# 04_Serial_Console.net
KiCad netlist of a schematic drawn in Altium Designer
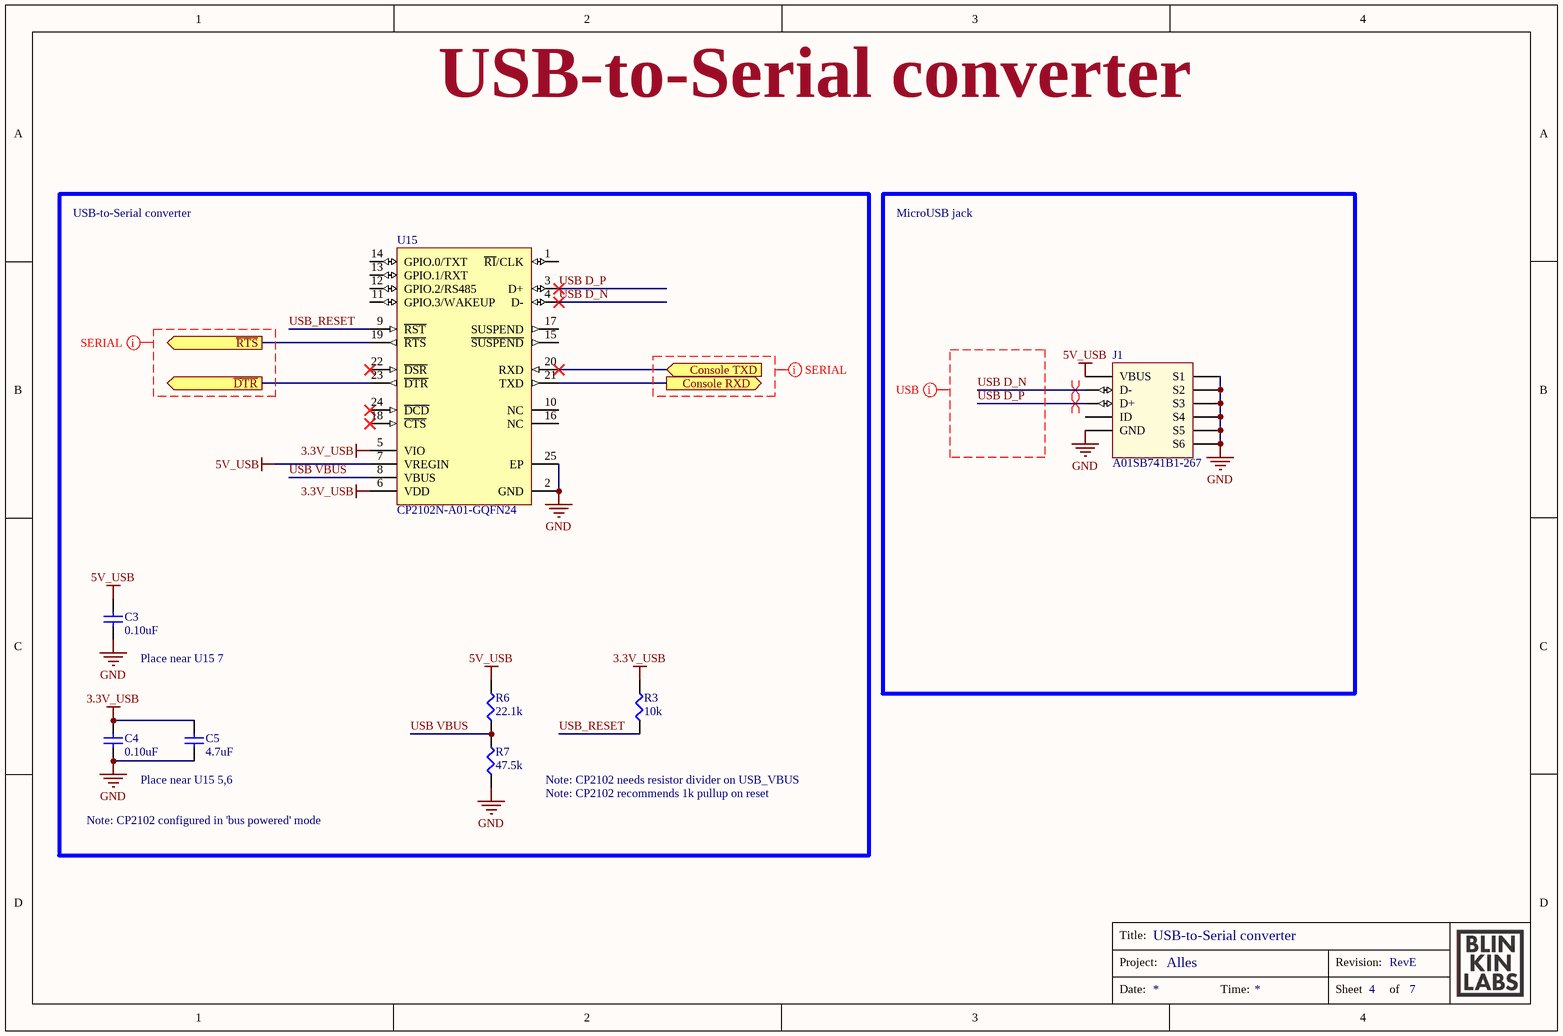
[diagram p0: [04] Serial Console.SchDoc]

(export (version "E")
  (design (tool "Eeschema 10.0.6"))
  (components
    (comp (ref "C3")
      (value "0.10uF")
      (footprint "CAPC1005X06L")
      (description "CAP CER 0.1UF 10V X5R 0402")
      (fields
        (field (name "DIGI-KEY PART NUMBER") "490-10009-1-ND")
        (field (name "MANUFACTURER") "Murata Electronics North America")
      )
      (libsource (lib "cap_murata") (part "CAPACITOR"))
    )
    (comp (ref "C4")
      (value "0.10uF")
      (footprint "CAPC1005X06L")
      (description "CAP CER 0.1UF 10V X5R 0402")
      (fields
        (field (name "DIGI-KEY PART NUMBER") "490-10009-1-ND")
        (field (name "MANUFACTURER") "Murata Electronics North America")
      )
      (libsource (lib "cap_murata") (part "CAPACITOR"))
    )
    (comp (ref "C5")
      (value "4.7uF")
      (footprint "CAPC1608X09L")
      (description "CAP CER 4.7UF 10V X5R 0603")
      (fields
        (field (name "PARTNUMBER") "GRM185R61A475KE11D")
        (field (name "DIGI-KEY PART NUMBER") "490-11988-1-ND")
      )
      (libsource (lib "cap_murata") (part "CAPACITOR"))
    )
    (comp (ref "J1")
      (value "A01SB741B1-267")
      (footprint "A01SB741B1-267")
      (description "Micro USB B type 四脚全插牛角")
      (fields (field (name "PARTNUMBER") "Unknown/Generic"))
      (libsource (lib "Blinkinlabs") (part "A01SB741B1-267"))
    )
    (comp (ref "R3")
      (value "10k")
      (footprint "ERJ2G(0402)_L")
      (description "RES SMD 10K OHM 5% 1/10W 0402")
      (fields (field (name "PARTNUMBER") "ERJ-2GEJ103X") (field (name "DIGI-KEY PART NUMBER") "P10KJCT-ND"))
      (libsource (lib "res_panasonic_erj_xls") (part "RESISTOR"))
    )
    (comp (ref "R6")
      (value "22.1k")
      (footprint "ERJ2G(0402)_L")
      (description "RES SMD 22.1K OHM 1% 1/10W 0402")
      (fields
        (field (name "PARTNUMBER") "ERJ-2RKF2212X")
        (field (name "DIGI-KEY PART NUMBER") "P22.1KLCT-ND")
      )
      (libsource (lib "res_panasonic_erj_xls") (part "RESISTOR"))
    )
    (comp (ref "R7")
      (value "47.5k")
      (footprint "ERJ2G(0402)_L")
      (description "RES SMD 47.5K OHM 1% 1/10W 0402")
      (fields
        (field (name "PARTNUMBER") "ERJ-2RKF4752X")
        (field (name "DIGI-KEY PART NUMBER") "P47.5KLCT-ND")
      )
      (libsource (lib "res_panasonic_erj_xls") (part "RESISTOR"))
    )
    (comp (ref "U15")
      (value "CP2102N-A01-GQFN24")
      (footprint "SLAB-QFN-24-2550x2550TP_A_V")
      (description "USBXpress(TM) Family, 4 GPIOs, 2.2 to 3.6 V, -40 to 85 degC, 24-Pin QFN, RoHS")
      (fields (field (name "MANUFACTURER") "Silicon Labs"))
      (libsource (lib "Altium Content Vault") (part "SLAB-CP2102N-QFN-24"))
    )
  )
  (nets
    (net (code "1") (name "/Console RXD") (class "Default")
      (node (ref "U15") (pin "21") (pinfunction "TXD_21") (pintype "output"))
    )
    (net (code "2") (name "/Console TXD") (class "Default")
      (node (ref "U15") (pin "20") (pinfunction "RXD_20") (pintype "input+no_connect"))
    )
    (net (code "3") (name "/USB D_N") (class "Default")
      (node (ref "J1") (pin "D-") (pinfunction "D-_D-") (pintype "bidirectional"))
      (node (ref "U15") (pin "4") (pinfunction "D-_4") (pintype "bidirectional"))
    )
    (net (code "4") (name "/USB D_P") (class "Default")
      (node (ref "J1") (pin "D+") (pinfunction "D+_D+") (pintype "bidirectional"))
      (node (ref "U15") (pin "3") (pinfunction "D+_3") (pintype "bidirectional"))
    )
    (net (code "5") (name "/USB VBUS") (class "Default")
      (node (ref "R6") (pin "1") (pinfunction "1_1") (pintype "passive"))
      (node (ref "R7") (pin "2") (pinfunction "2_2") (pintype "passive"))
      (node (ref "U15") (pin "8") (pinfunction "VBUS_8") (pintype "power_in"))
    )
    (net (code "6") (name "/USB_RESET") (class "Default")
      (node (ref "R3") (pin "1") (pinfunction "1_1") (pintype "passive"))
      (node (ref "U15") (pin "9") (pinfunction "~{RST}_9") (pintype "input"))
    )
    (net (code "7") (name "/~{DTR}") (class "Default")
      (node (ref "U15") (pin "23") (pinfunction "~{DTR}_23") (pintype "output"))
    )
    (net (code "8") (name "/~{RTS}") (class "Default")
      (node (ref "U15") (pin "19") (pinfunction "~{RTS}_19") (pintype "output"))
    )
    (net (code "9") (name "3.3V_USB") (class "Default")
      (node (ref "C4") (pin "2") (pinfunction "2_2") (pintype "passive"))
      (node (ref "C5") (pin "1") (pinfunction "1_1") (pintype "passive"))
      (node (ref "R3") (pin "2") (pinfunction "2_2") (pintype "passive"))
      (node (ref "U15") (pin "5") (pinfunction "VIO_5") (pintype "power_in"))
      (node (ref "U15") (pin "6") (pinfunction "VDD_6") (pintype "power_in"))
    )
    (net (code "10") (name "5V_USB") (class "Default")
      (node (ref "C3") (pin "2") (pinfunction "2_2") (pintype "passive"))
      (node (ref "J1") (pin "VBUS") (pinfunction "VBUS_VBUS") (pintype "power_in"))
      (node (ref "R6") (pin "2") (pinfunction "2_2") (pintype "passive"))
      (node (ref "U15") (pin "7") (pinfunction "VREGIN_7") (pintype "power_in"))
    )
    (net (code "11") (name "GND") (class "Default")
      (node (ref "C3") (pin "1") (pinfunction "1_1") (pintype "passive"))
      (node (ref "C4") (pin "1") (pinfunction "1_1") (pintype "passive"))
      (node (ref "C5") (pin "2") (pinfunction "2_2") (pintype "passive"))
      (node (ref "J1") (pin "GND") (pinfunction "GND_GND") (pintype "power_in"))
      (node (ref "J1") (pin "S1") (pinfunction "S1_S1") (pintype "passive"))
      (node (ref "J1") (pin "S2") (pinfunction "S2_S2") (pintype "passive"))
      (node (ref "J1") (pin "S3") (pinfunction "S3_S3") (pintype "passive"))
      (node (ref "J1") (pin "S4") (pinfunction "S4_S4") (pintype "passive"))
      (node (ref "J1") (pin "S5") (pinfunction "S5_S5") (pintype "passive"))
      (node (ref "J1") (pin "S6") (pinfunction "S6_S6") (pintype "passive"))
      (node (ref "R7") (pin "1") (pinfunction "1_1") (pintype "passive"))
      (node (ref "U15") (pin "2") (pinfunction "GND_2") (pintype "power_in"))
      (node (ref "U15") (pin "25") (pinfunction "EP_25") (pintype "power_in"))
    )
    (net (code "12") (name "unconnected-(J1-PadID)") (class "Default")
      (node (ref "J1") (pin "ID") (pinfunction "ID_ID") (pintype "passive"))
    )
    (net (code "13") (name "unconnected-(U15-GPIO.0{slash}TXT-Pad14)") (class "Default")
      (node (ref "U15") (pin "14") (pinfunction "GPIO.0/TXT_14") (pintype "bidirectional"))
    )
    (net (code "14") (name "unconnected-(U15-GPIO.1{slash}RXT-Pad13)") (class "Default")
      (node (ref "U15") (pin "13") (pinfunction "GPIO.1/RXT_13") (pintype "bidirectional"))
    )
    (net (code "15") (name "unconnected-(U15-GPIO.2{slash}RS485-Pad12)") (class "Default")
      (node (ref "U15") (pin "12") (pinfunction "GPIO.2/RS485_12") (pintype "bidirectional"))
    )
    (net (code "16") (name "unconnected-(U15-GPIO.3{slash}WAKEUP-Pad11)") (class "Default")
      (node (ref "U15") (pin "11") (pinfunction "GPIO.3/WAKEUP_11") (pintype "bidirectional"))
    )
    (net (code "17") (name "unconnected-(U15-NC-Pad10)") (class "Default")
      (node (ref "U15") (pin "10") (pinfunction "NC_10") (pintype "passive"))
    )
    (net (code "18") (name "unconnected-(U15-NC-Pad16)") (class "Default")
      (node (ref "U15") (pin "16") (pinfunction "NC_16") (pintype "passive"))
    )
    (net (code "19") (name "unconnected-(U15-SUSPEND-Pad17)") (class "Default")
      (node (ref "U15") (pin "17") (pinfunction "SUSPEND_17") (pintype "output"))
    )
    (net (code "20") (name "unconnected-(U15-~{CTS}-Pad18)") (class "Default")
      (node (ref "U15") (pin "18") (pinfunction "~{CTS}_18") (pintype "input+no_connect"))
    )
    (net (code "21") (name "unconnected-(U15-~{DCD}-Pad24)") (class "Default")
      (node (ref "U15") (pin "24") (pinfunction "~{DCD}_24") (pintype "input+no_connect"))
    )
    (net (code "22") (name "unconnected-(U15-~{DSR}-Pad22)") (class "Default")
      (node (ref "U15") (pin "22") (pinfunction "~{DSR}_22") (pintype "input+no_connect"))
    )
    (net (code "23") (name "unconnected-(U15-~{RI}{slash}CLK-Pad1)") (class "Default")
      (node (ref "U15") (pin "1") (pinfunction "~{RI}/CLK_1") (pintype "bidirectional"))
    )
    (net (code "24") (name "unconnected-(U15-~{SUSPEND}-Pad15)") (class "Default")
      (node (ref "U15") (pin "15") (pinfunction "~{SUSPEND}_15") (pintype "output"))
    )
  )
)
